# Shruthi-Analog-SMR4-mkII-12V-DO-NOT-BUIL.net
KiCad netlist of a schematic drawn in EAGLE
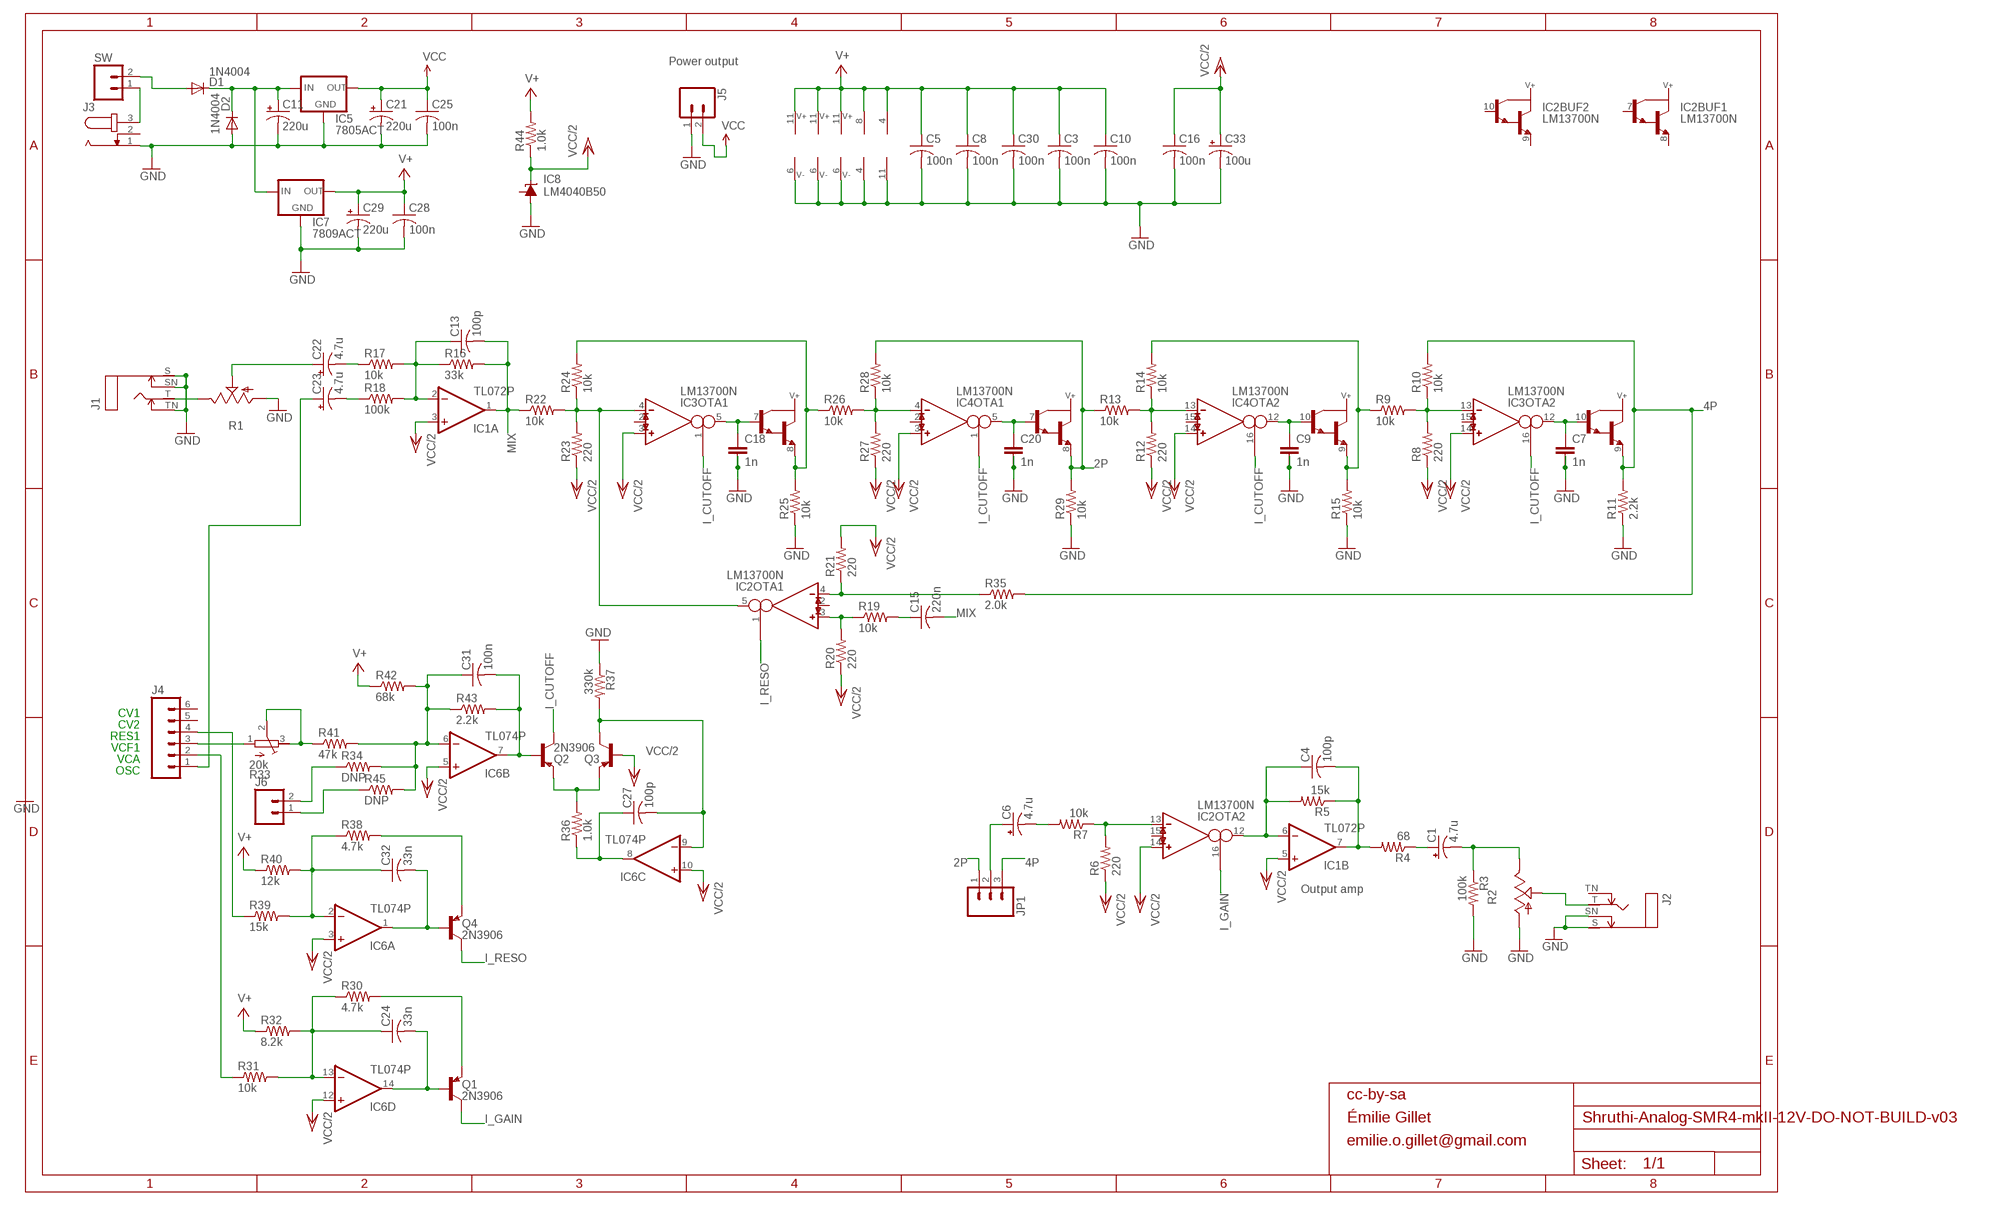
[diagram p0: schematic, sheet 1]

(export (version "E")
  (design (tool "Eeschema 10.0.6"))
  (components
    (comp (ref "C1")
      (value "4.7u")
      (footprint "eagle-import:E2,5-6")
      (libsource (lib "eagle-import") (part "CPOL-USE2.5-6"))
    )
    (comp (ref "C3")
      (value "100n")
      (footprint "eagle-import:C025-025X050")
      (libsource (lib "eagle-import") (part "C-US025-025X050"))
    )
    (comp (ref "C4")
      (value "100p")
      (footprint "eagle-import:C025-025X050")
      (libsource (lib "eagle-import") (part "C-US025-025X050"))
    )
    (comp (ref "C5")
      (value "100n")
      (footprint "eagle-import:C025-025X050")
      (libsource (lib "eagle-import") (part "C-US025-025X050"))
    )
    (comp (ref "C6")
      (value "4.7u")
      (footprint "eagle-import:E2,5-6")
      (libsource (lib "eagle-import") (part "CPOL-USE2.5-6"))
    )
    (comp (ref "C7")
      (value "1n")
      (footprint "eagle-import:C2.5_5-2")
      (libsource (lib "eagle-import") (part "C-2.5-5/2"))
    )
    (comp (ref "C8")
      (value "100n")
      (footprint "eagle-import:C025-025X050")
      (libsource (lib "eagle-import") (part "C-US025-025X050"))
    )
    (comp (ref "C9")
      (value "1n")
      (footprint "eagle-import:C2.5_5-2")
      (libsource (lib "eagle-import") (part "C-2.5-5/2"))
    )
    (comp (ref "C10")
      (value "100n")
      (footprint "eagle-import:C025-025X050")
      (libsource (lib "eagle-import") (part "C-US025-025X050"))
    )
    (comp (ref "C11")
      (value "220u")
      (footprint "eagle-import:E5-10,5")
      (libsource (lib "eagle-import") (part "CPOL-USE5-10.5"))
    )
    (comp (ref "C13")
      (value "100p")
      (footprint "eagle-import:C025-025X050")
      (libsource (lib "eagle-import") (part "C-US025-025X050"))
    )
    (comp (ref "C15")
      (value "220n")
      (footprint "eagle-import:C025-025X050")
      (libsource (lib "eagle-import") (part "C-US025-025X050"))
    )
    (comp (ref "C16")
      (value "100n")
      (footprint "eagle-import:C025-025X050")
      (libsource (lib "eagle-import") (part "C-US025-025X050"))
    )
    (comp (ref "C18")
      (value "1n")
      (footprint "eagle-import:C2.5_5-2")
      (libsource (lib "eagle-import") (part "C-2.5-5/2"))
    )
    (comp (ref "C20")
      (value "1n")
      (footprint "eagle-import:C2.5_5-2")
      (libsource (lib "eagle-import") (part "C-2.5-5/2"))
    )
    (comp (ref "C21")
      (value "220u")
      (footprint "eagle-import:E5-10,5")
      (libsource (lib "eagle-import") (part "CPOL-USE5-10.5"))
    )
    (comp (ref "C22")
      (value "4.7u")
      (footprint "eagle-import:E2,5-6")
      (libsource (lib "eagle-import") (part "CPOL-USE2.5-6"))
    )
    (comp (ref "C23")
      (value "4.7u")
      (footprint "eagle-import:E2,5-6")
      (libsource (lib "eagle-import") (part "CPOL-USE2.5-6"))
    )
    (comp (ref "C24")
      (value "33n")
      (footprint "eagle-import:C050-025X075")
      (libsource (lib "eagle-import") (part "C-US050-025X075"))
    )
    (comp (ref "C25")
      (value "100n")
      (footprint "eagle-import:C025-025X050")
      (libsource (lib "eagle-import") (part "C-US025-025X050"))
    )
    (comp (ref "C27")
      (value "100p")
      (footprint "eagle-import:C025-025X050")
      (libsource (lib "eagle-import") (part "C-US025-025X050"))
    )
    (comp (ref "C28")
      (value "100n")
      (footprint "eagle-import:C025-025X050")
      (libsource (lib "eagle-import") (part "C-US025-025X050"))
    )
    (comp (ref "C29")
      (value "220u")
      (footprint "eagle-import:E5-10,5")
      (libsource (lib "eagle-import") (part "CPOL-USE5-10.5"))
    )
    (comp (ref "C30")
      (value "100n")
      (footprint "eagle-import:C025-025X050")
      (libsource (lib "eagle-import") (part "C-US025-025X050"))
    )
    (comp (ref "C31")
      (value "100n")
      (footprint "eagle-import:C025-025X050")
      (libsource (lib "eagle-import") (part "C-US025-025X050"))
    )
    (comp (ref "C32")
      (value "33n")
      (footprint "eagle-import:C050-025X075")
      (libsource (lib "eagle-import") (part "C-US050-025X075"))
    )
    (comp (ref "C33")
      (value "100u")
      (footprint "eagle-import:E2,5-6")
      (libsource (lib "eagle-import") (part "CPOL-USE2.5-6"))
    )
    (comp (ref "D1")
      (value "1N4004")
      (footprint "eagle-import:DO41-10")
      (libsource (lib "eagle-import") (part "1N4004"))
    )
    (comp (ref "D2")
      (value "1N4004")
      (footprint "eagle-import:DO41-10")
      (libsource (lib "eagle-import") (part "1N4004"))
    )
    (comp (ref "IC1")
      (value "TL072P")
      (footprint "eagle-import:DIL08")
      (libsource (lib "eagle-import") (part "TL072P"))
    )
    (comp (ref "IC2")
      (value "LM13700N")
      (footprint "eagle-import:DIL16")
      (libsource (lib "eagle-import") (part "LM13700N"))
    )
    (comp (ref "IC3")
      (value "LM13700N")
      (footprint "eagle-import:DIL16")
      (libsource (lib "eagle-import") (part "LM13700N"))
    )
    (comp (ref "IC4")
      (value "LM13700N")
      (footprint "eagle-import:DIL16")
      (libsource (lib "eagle-import") (part "LM13700N"))
    )
    (comp (ref "IC5")
      (value "7805ACT")
      (footprint "eagle-import:78XXS")
      (libsource (lib "eagle-import") (part "78XXS"))
    )
    (comp (ref "IC6")
      (value "TL074P")
      (footprint "eagle-import:DIL14")
      (libsource (lib "eagle-import") (part "TL084P"))
    )
    (comp (ref "IC7")
      (value "7809ACT")
      (footprint "eagle-import:78XXS")
      (libsource (lib "eagle-import") (part "78XXS"))
    )
    (comp (ref "IC8")
      (value "LM4040B50")
      (footprint "eagle-import:LP_O-PBCY-W3")
      (libsource (lib "eagle-import") (part "LM4041ILPB"))
    )
    (comp (ref "J1")
      (value "MONOSWS")
      (footprint "eagle-import:NMJ4HC-S")
      (libsource (lib "eagle-import") (part "MONOSWS"))
    )
    (comp (ref "J2")
      (value "MONOSWS")
      (footprint "eagle-import:NMJ4HC-S")
      (libsource (lib "eagle-import") (part "MONOSWS"))
    )
    (comp (ref "J3")
      (value "JACK-PLUG2")
      (footprint "eagle-import:SPC4078_BIG_HOLES")
      (libsource (lib "eagle-import") (part "JACK-PLUG2"))
    )
    (comp (ref "J4")
      (value "M06SIP")
      (footprint "eagle-import:1X06")
      (libsource (lib "eagle-import") (part "M06SIP"))
    )
    (comp (ref "J5")
      (value "M02PTH")
      (footprint "eagle-import:1X02")
      (libsource (lib "eagle-import") (part "M02PTH"))
    )
    (comp (ref "J6")
      (value "M02PTH")
      (footprint "eagle-import:1X02")
      (libsource (lib "eagle-import") (part "M02PTH"))
    )
    (comp (ref "JP1")
      (value "M03PTH")
      (footprint "eagle-import:1X03")
      (libsource (lib "eagle-import") (part "M03PTH"))
    )
    (comp (ref "Q1")
      (value "2N3906")
      (footprint "eagle-import:TO92-")
      (libsource (lib "eagle-import") (part "2N3906-"))
    )
    (comp (ref "Q2")
      (value "2N3906")
      (footprint "eagle-import:TO92-")
      (libsource (lib "eagle-import") (part "2N3906-"))
    )
    (comp (ref "Q3")
      (value "2N3906")
      (footprint "eagle-import:TO92-")
      (libsource (lib "eagle-import") (part "2N3906-"))
    )
    (comp (ref "Q4")
      (value "2N3906")
      (footprint "eagle-import:TO92-")
      (libsource (lib "eagle-import") (part "2N3906-"))
    )
    (comp (ref "R1")
      (value "POT_USCABLED")
      (footprint "eagle-import:CABLE_POT_6MM")
      (libsource (lib "eagle-import") (part "POT_USCABLED"))
    )
    (comp (ref "R2")
      (value "POT_USCABLED")
      (footprint "eagle-import:CABLE_POT_6MM")
      (libsource (lib "eagle-import") (part "POT_USCABLED"))
    )
    (comp (ref "R3")
      (value "100k")
      (footprint "eagle-import:0204_7")
      (libsource (lib "eagle-import") (part "R-US_0204/7"))
    )
    (comp (ref "R4")
      (value "68")
      (footprint "eagle-import:0204_7")
      (libsource (lib "eagle-import") (part "R-US_0204/7"))
    )
    (comp (ref "R5")
      (value "15k")
      (footprint "eagle-import:0204_7")
      (libsource (lib "eagle-import") (part "R-US_0204/7"))
    )
    (comp (ref "R6")
      (value "220")
      (footprint "eagle-import:0204_7")
      (libsource (lib "eagle-import") (part "R-US_0204/7"))
    )
    (comp (ref "R7")
      (value "10k")
      (footprint "eagle-import:0204_7")
      (libsource (lib "eagle-import") (part "R-US_0204/7"))
    )
    (comp (ref "R8")
      (value "220")
      (footprint "eagle-import:0204_7")
      (libsource (lib "eagle-import") (part "R-US_0204/7"))
    )
    (comp (ref "R9")
      (value "10k")
      (footprint "eagle-import:0204_7")
      (libsource (lib "eagle-import") (part "R-US_0204/7"))
    )
    (comp (ref "R10")
      (value "10k")
      (footprint "eagle-import:0204_7")
      (libsource (lib "eagle-import") (part "R-US_0204/7"))
    )
    (comp (ref "R11")
      (value "2.2k")
      (footprint "eagle-import:0204_7")
      (libsource (lib "eagle-import") (part "R-US_0204/7"))
    )
    (comp (ref "R12")
      (value "220")
      (footprint "eagle-import:0204_7")
      (libsource (lib "eagle-import") (part "R-US_0204/7"))
    )
    (comp (ref "R13")
      (value "10k")
      (footprint "eagle-import:0204_7")
      (libsource (lib "eagle-import") (part "R-US_0204/7"))
    )
    (comp (ref "R14")
      (value "10k")
      (footprint "eagle-import:0204_7")
      (libsource (lib "eagle-import") (part "R-US_0204/7"))
    )
    (comp (ref "R15")
      (value "10k")
      (footprint "eagle-import:0204_7")
      (libsource (lib "eagle-import") (part "R-US_0204/7"))
    )
    (comp (ref "R16")
      (value "33k")
      (footprint "eagle-import:0204_7")
      (libsource (lib "eagle-import") (part "R-US_0204/7"))
    )
    (comp (ref "R17")
      (value "10k")
      (footprint "eagle-import:0204_7")
      (libsource (lib "eagle-import") (part "R-US_0204/7"))
    )
    (comp (ref "R18")
      (value "100k")
      (footprint "eagle-import:0204_7")
      (libsource (lib "eagle-import") (part "R-US_0204/7"))
    )
    (comp (ref "R19")
      (value "10k")
      (footprint "eagle-import:0204_7")
      (libsource (lib "eagle-import") (part "R-US_0204/7"))
    )
    (comp (ref "R20")
      (value "220")
      (footprint "eagle-import:0204_7")
      (libsource (lib "eagle-import") (part "R-US_0204/7"))
    )
    (comp (ref "R21")
      (value "220")
      (footprint "eagle-import:0204_7")
      (libsource (lib "eagle-import") (part "R-US_0204/7"))
    )
    (comp (ref "R22")
      (value "10k")
      (footprint "eagle-import:0204_7")
      (libsource (lib "eagle-import") (part "R-US_0204/7"))
    )
    (comp (ref "R23")
      (value "220")
      (footprint "eagle-import:0204_7")
      (libsource (lib "eagle-import") (part "R-US_0204/7"))
    )
    (comp (ref "R24")
      (value "10k")
      (footprint "eagle-import:0204_7")
      (libsource (lib "eagle-import") (part "R-US_0204/7"))
    )
    (comp (ref "R25")
      (value "10k")
      (footprint "eagle-import:0204_7")
      (libsource (lib "eagle-import") (part "R-US_0204/7"))
    )
    (comp (ref "R26")
      (value "10k")
      (footprint "eagle-import:0204_7")
      (libsource (lib "eagle-import") (part "R-US_0204/7"))
    )
    (comp (ref "R27")
      (value "220")
      (footprint "eagle-import:0204_7")
      (libsource (lib "eagle-import") (part "R-US_0204/7"))
    )
    (comp (ref "R28")
      (value "10k")
      (footprint "eagle-import:0204_7")
      (libsource (lib "eagle-import") (part "R-US_0204/7"))
    )
    (comp (ref "R29")
      (value "10k")
      (footprint "eagle-import:0204_7")
      (libsource (lib "eagle-import") (part "R-US_0204/7"))
    )
    (comp (ref "R30")
      (value "4.7k")
      (footprint "eagle-import:0204_7")
      (libsource (lib "eagle-import") (part "R-US_0204/7"))
    )
    (comp (ref "R31")
      (value "10k")
      (footprint "eagle-import:0204_7")
      (libsource (lib "eagle-import") (part "R-US_0204/7"))
    )
    (comp (ref "R32")
      (value "8.2k")
      (footprint "eagle-import:0204_7")
      (libsource (lib "eagle-import") (part "R-US_0204/7"))
    )
    (comp (ref "R33")
      (value "20k")
      (footprint "eagle-import:RTRIM3296W")
      (libsource (lib "eagle-import") (part "R-TRIMM3296W"))
    )
    (comp (ref "R34")
      (value "DNP")
      (footprint "eagle-import:0204V")
      (libsource (lib "eagle-import") (part "R-US_0204/2V"))
    )
    (comp (ref "R35")
      (value "2.0k")
      (footprint "eagle-import:0204_7")
      (libsource (lib "eagle-import") (part "R-US_0204/7"))
    )
    (comp (ref "R36")
      (value "1.0k")
      (footprint "eagle-import:0204_7")
      (libsource (lib "eagle-import") (part "R-US_0204/7"))
    )
    (comp (ref "R37")
      (value "330k")
      (footprint "eagle-import:0204_7")
      (libsource (lib "eagle-import") (part "R-US_0204/7"))
    )
    (comp (ref "R38")
      (value "4.7k")
      (footprint "eagle-import:0204_7")
      (libsource (lib "eagle-import") (part "R-US_0204/7"))
    )
    (comp (ref "R39")
      (value "15k")
      (footprint "eagle-import:0204_7")
      (libsource (lib "eagle-import") (part "R-US_0204/7"))
    )
    (comp (ref "R40")
      (value "12k")
      (footprint "eagle-import:0204_7")
      (libsource (lib "eagle-import") (part "R-US_0204/7"))
    )
    (comp (ref "R41")
      (value "47k")
      (footprint "eagle-import:0204_7")
      (libsource (lib "eagle-import") (part "R-US_0204/7"))
    )
    (comp (ref "R42")
      (value "68k")
      (footprint "eagle-import:0204_7")
      (libsource (lib "eagle-import") (part "R-US_0204/7"))
    )
    (comp (ref "R43")
      (value "2.2k")
      (footprint "eagle-import:0204_7")
      (libsource (lib "eagle-import") (part "R-US_0204/7"))
    )
    (comp (ref "R44")
      (value "1.0k")
      (footprint "eagle-import:0204_7")
      (libsource (lib "eagle-import") (part "R-US_0204/7"))
    )
    (comp (ref "R45")
      (value "DNP")
      (footprint "eagle-import:0204V")
      (libsource (lib "eagle-import") (part "R-US_0204/2V"))
    )
    (comp (ref "SW")
      (value "M02PTH")
      (footprint "eagle-import:1X02")
      (libsource (lib "eagle-import") (part "M02PTH"))
    )
  )
  (nets
    (net (code "1") (name "/2P") (class "Default")
      (node (ref "IC4") (pin "8") (pinfunction "E_8") (pintype "passive"))
      (node (ref "JP1") (pin "1") (pinfunction "1_1") (pintype "passive"))
      (node (ref "R13") (pin "1") (pinfunction "1_1") (pintype "passive"))
      (node (ref "R28") (pin "2") (pinfunction "2_2") (pintype "passive"))
      (node (ref "R29") (pin "2") (pinfunction "2_2") (pintype "passive"))
    )
    (net (code "2") (name "/4P") (class "Default")
      (node (ref "IC3") (pin "9") (pinfunction "E_9") (pintype "passive"))
      (node (ref "JP1") (pin "3") (pinfunction "3_3") (pintype "passive"))
      (node (ref "R10") (pin "2") (pinfunction "2_2") (pintype "passive"))
      (node (ref "R11") (pin "2") (pinfunction "2_2") (pintype "passive"))
      (node (ref "R35") (pin "2") (pinfunction "2_2") (pintype "passive"))
    )
    (net (code "3") (name "/I_CUTOFF") (class "Default")
      (node (ref "IC3") (pin "1") (pinfunction "I_BIAS_1") (pintype "input"))
      (node (ref "IC3") (pin "16") (pinfunction "I_BIAS_16") (pintype "input"))
      (node (ref "IC4") (pin "1") (pinfunction "I_BIAS_1") (pintype "input"))
      (node (ref "IC4") (pin "16") (pinfunction "I_BIAS_16") (pintype "input"))
      (node (ref "Q2") (pin "1") (pinfunction "C_1") (pintype "passive"))
    )
    (net (code "4") (name "/I_GAIN") (class "Default")
      (node (ref "IC2") (pin "16") (pinfunction "I_BIAS_16") (pintype "input"))
      (node (ref "Q1") (pin "1") (pinfunction "C_1") (pintype "passive"))
    )
    (net (code "5") (name "/I_RESO") (class "Default")
      (node (ref "IC2") (pin "1") (pinfunction "I_BIAS_1") (pintype "input"))
      (node (ref "Q4") (pin "1") (pinfunction "C_1") (pintype "passive"))
    )
    (net (code "6") (name "/MIX") (class "Default")
      (node (ref "C13") (pin "2") (pinfunction "2_2") (pintype "passive"))
      (node (ref "C15") (pin "2") (pinfunction "2_2") (pintype "passive"))
      (node (ref "IC1") (pin "1") (pinfunction "OUT_1") (pintype "output"))
      (node (ref "R16") (pin "2") (pinfunction "2_2") (pintype "passive"))
      (node (ref "R22") (pin "1") (pinfunction "1_1") (pintype "passive"))
    )
    (net (code "7") (name "GND") (class "Default")
      (node (ref "C10") (pin "2") (pinfunction "2_2") (pintype "passive"))
      (node (ref "C11") (pin "-") (pinfunction "-_-") (pintype "passive"))
      (node (ref "C16") (pin "2") (pinfunction "2_2") (pintype "passive"))
      (node (ref "C18") (pin "2") (pinfunction "2_2") (pintype "passive"))
      (node (ref "C18") (pin "3") (pinfunction "3_3") (pintype "passive"))
      (node (ref "C20") (pin "2") (pinfunction "2_2") (pintype "passive"))
      (node (ref "C20") (pin "3") (pinfunction "3_3") (pintype "passive"))
      (node (ref "C21") (pin "-") (pinfunction "-_-") (pintype "passive"))
      (node (ref "C25") (pin "2") (pinfunction "2_2") (pintype "passive"))
      (node (ref "C28") (pin "2") (pinfunction "2_2") (pintype "passive"))
      (node (ref "C29") (pin "-") (pinfunction "-_-") (pintype "passive"))
      (node (ref "C3") (pin "2") (pinfunction "2_2") (pintype "passive"))
      (node (ref "C30") (pin "2") (pinfunction "2_2") (pintype "passive"))
      (node (ref "C33") (pin "-") (pinfunction "-_-") (pintype "passive"))
      (node (ref "C5") (pin "2") (pinfunction "2_2") (pintype "passive"))
      (node (ref "C7") (pin "2") (pinfunction "2_2") (pintype "passive"))
      (node (ref "C7") (pin "3") (pinfunction "3_3") (pintype "passive"))
      (node (ref "C8") (pin "2") (pinfunction "2_2") (pintype "passive"))
      (node (ref "C9") (pin "2") (pinfunction "2_2") (pintype "passive"))
      (node (ref "C9") (pin "3") (pinfunction "3_3") (pintype "passive"))
      (node (ref "D2") (pin "A") (pinfunction "A_A") (pintype "passive"))
      (node (ref "IC1") (pin "4") (pinfunction "V-_4") (pintype "power_in"))
      (node (ref "IC2") (pin "6") (pinfunction "V-_6") (pintype "power_in"))
      (node (ref "IC3") (pin "6") (pinfunction "V-_6") (pintype "power_in"))
      (node (ref "IC4") (pin "6") (pinfunction "V-_6") (pintype "power_in"))
      (node (ref "IC5") (pin "GND") (pinfunction "GND_GND") (pintype "input"))
      (node (ref "IC6") (pin "11") (pinfunction "V-_11") (pintype "power_in"))
      (node (ref "IC7") (pin "GND") (pinfunction "GND_GND") (pintype "input"))
      (node (ref "IC8") (pin "3") (pinfunction "A_3") (pintype "passive"))
      (node (ref "J1") (pin "S") (pinfunction "S_S") (pintype "passive"))
      (node (ref "J1") (pin "SN") (pinfunction "SN_SN") (pintype "passive"))
      (node (ref "J1") (pin "TN") (pinfunction "TN_TN") (pintype "passive"))
      (node (ref "J2") (pin "S") (pinfunction "S_S") (pintype "passive"))
      (node (ref "J2") (pin "SN") (pinfunction "SN_SN") (pintype "passive"))
      (node (ref "J3") (pin "1") (pinfunction "1_1") (pintype "passive"))
      (node (ref "J5") (pin "1") (pinfunction "1_1") (pintype "passive"))
      (node (ref "R1") (pin "A") (pinfunction "A_A") (pintype "passive"))
      (node (ref "R11") (pin "1") (pinfunction "1_1") (pintype "passive"))
      (node (ref "R15") (pin "1") (pinfunction "1_1") (pintype "passive"))
      (node (ref "R2") (pin "A") (pinfunction "A_A") (pintype "passive"))
      (node (ref "R25") (pin "1") (pinfunction "1_1") (pintype "passive"))
      (node (ref "R29") (pin "1") (pinfunction "1_1") (pintype "passive"))
      (node (ref "R3") (pin "2") (pinfunction "2_2") (pintype "passive"))
      (node (ref "R37") (pin "1") (pinfunction "1_1") (pintype "passive"))
    )
    (net (code "8") (name "Net-(C1-Pad+)") (class "Default")
      (node (ref "C1") (pin "+") (pinfunction "+_+") (pintype "passive"))
      (node (ref "R4") (pin "1") (pinfunction "1_1") (pintype "passive"))
    )
    (net (code "9") (name "Net-(C1-Pad-)") (class "Default")
      (node (ref "C1") (pin "-") (pinfunction "-_-") (pintype "passive"))
      (node (ref "R2") (pin "E") (pinfunction "E_E") (pintype "passive"))
      (node (ref "R3") (pin "1") (pinfunction "1_1") (pintype "passive"))
    )
    (net (code "10") (name "Net-(C6-Pad+)") (class "Default")
      (node (ref "C6") (pin "+") (pinfunction "+_+") (pintype "passive"))
      (node (ref "JP1") (pin "2") (pinfunction "2_2") (pintype "passive"))
    )
    (net (code "11") (name "Net-(C6-Pad-)") (class "Default")
      (node (ref "C6") (pin "-") (pinfunction "-_-") (pintype "passive"))
      (node (ref "R7") (pin "2") (pinfunction "2_2") (pintype "passive"))
    )
    (net (code "12") (name "Net-(C11-Pad+)") (class "Default")
      (node (ref "C11") (pin "+") (pinfunction "+_+") (pintype "passive"))
      (node (ref "D1") (pin "C") (pinfunction "C_C") (pintype "passive"))
      (node (ref "D2") (pin "C") (pinfunction "C_C") (pintype "passive"))
      (node (ref "IC5") (pin "IN") (pinfunction "IN_IN") (pintype "input"))
      (node (ref "IC7") (pin "IN") (pinfunction "IN_IN") (pintype "input"))
    )
    (net (code "13") (name "Net-(C15-Pad1)") (class "Default")
      (node (ref "C15") (pin "1") (pinfunction "1_1") (pintype "passive"))
      (node (ref "R19") (pin "2") (pinfunction "2_2") (pintype "passive"))
    )
    (net (code "14") (name "Net-(C22-Pad+)") (class "Default")
      (node (ref "C22") (pin "+") (pinfunction "+_+") (pintype "passive"))
      (node (ref "R1") (pin "S") (pinfunction "S_S") (pintype "passive"))
    )
    (net (code "15") (name "Net-(C22-Pad-)") (class "Default")
      (node (ref "C22") (pin "-") (pinfunction "-_-") (pintype "passive"))
      (node (ref "R17") (pin "1") (pinfunction "1_1") (pintype "passive"))
    )
    (net (code "16") (name "Net-(C23-Pad+)") (class "Default")
      (node (ref "C23") (pin "+") (pinfunction "+_+") (pintype "passive"))
      (node (ref "J4") (pin "1") (pinfunction "1_1") (pintype "passive"))
    )
    (net (code "17") (name "Net-(C23-Pad-)") (class "Default")
      (node (ref "C23") (pin "-") (pinfunction "-_-") (pintype "passive"))
      (node (ref "R18") (pin "1") (pinfunction "1_1") (pintype "passive"))
    )
    (net (code "18") (name "Net-(D1-PadA)") (class "Default")
      (node (ref "D1") (pin "A") (pinfunction "A_A") (pintype "passive"))
      (node (ref "SW") (pin "2") (pinfunction "2_2") (pintype "passive"))
    )
    (net (code "19") (name "Net-(IC1A--IN)") (class "Default")
      (node (ref "C13") (pin "1") (pinfunction "1_1") (pintype "passive"))
      (node (ref "IC1") (pin "2") (pinfunction "-IN_2") (pintype "input"))
      (node (ref "R16") (pin "1") (pinfunction "1_1") (pintype "passive"))
      (node (ref "R17") (pin "2") (pinfunction "2_2") (pintype "passive"))
      (node (ref "R18") (pin "2") (pinfunction "2_2") (pintype "passive"))
    )
    (net (code "20") (name "Net-(IC1B--IN)") (class "Default")
      (node (ref "C4") (pin "1") (pinfunction "1_1") (pintype "passive"))
      (node (ref "IC1") (pin "6") (pinfunction "-IN_6") (pintype "input"))
      (node (ref "IC2") (pin "12") (pinfunction "OUT_12") (pintype "output"))
      (node (ref "R5") (pin "2") (pinfunction "2_2") (pintype "passive"))
    )
    (net (code "21") (name "Net-(IC1B-OUT)") (class "Default")
      (node (ref "C4") (pin "2") (pinfunction "2_2") (pintype "passive"))
      (node (ref "IC1") (pin "7") (pinfunction "OUT_7") (pintype "output"))
      (node (ref "R4") (pin "2") (pinfunction "2_2") (pintype "passive"))
      (node (ref "R5") (pin "1") (pinfunction "1_1") (pintype "passive"))
    )
    (net (code "22") (name "Net-(IC2C-IN_N)") (class "Default")
      (node (ref "IC2") (pin "4") (pinfunction "IN_N_4") (pintype "input"))
      (node (ref "R21") (pin "1") (pinfunction "1_1") (pintype "passive"))
      (node (ref "R35") (pin "1") (pinfunction "1_1") (pintype "passive"))
    )
    (net (code "23") (name "Net-(IC2C-IN_P)") (class "Default")
      (node (ref "IC2") (pin "3") (pinfunction "IN_P_3") (pintype "input"))
      (node (ref "R19") (pin "1") (pinfunction "1_1") (pintype "passive"))
      (node (ref "R20") (pin "2") (pinfunction "2_2") (pintype "passive"))
    )
    (net (code "24") (name "Net-(IC2C-OUT)") (class "Default")
      (node (ref "IC2") (pin "5") (pinfunction "OUT_5") (pintype "output"))
      (node (ref "IC3") (pin "4") (pinfunction "IN_N_4") (pintype "input"))
      (node (ref "R22") (pin "2") (pinfunction "2_2") (pintype "passive"))
      (node (ref "R23") (pin "2") (pinfunction "2_2") (pintype "passive"))
      (node (ref "R24") (pin "1") (pinfunction "1_1") (pintype "passive"))
    )
    (net (code "25") (name "Net-(IC2D-IN_N)") (class "Default")
      (node (ref "IC2") (pin "13") (pinfunction "IN_N_13") (pintype "input"))
      (node (ref "R6") (pin "2") (pinfunction "2_2") (pintype "passive"))
      (node (ref "R7") (pin "1") (pinfunction "1_1") (pintype "passive"))
    )
    (net (code "26") (name "Net-(IC3A-B)") (class "Default")
      (node (ref "C18") (pin "1") (pinfunction "1_1") (pintype "passive"))
      (node (ref "IC3") (pin "5") (pinfunction "OUT_5") (pintype "output"))
      (node (ref "IC3") (pin "7") (pinfunction "B_7") (pintype "passive"))
    )
    (net (code "27") (name "Net-(IC3A-E)") (class "Default")
      (node (ref "IC3") (pin "8") (pinfunction "E_8") (pintype "passive"))
      (node (ref "R24") (pin "2") (pinfunction "2_2") (pintype "passive"))
      (node (ref "R25") (pin "2") (pinfunction "2_2") (pintype "passive"))
      (node (ref "R26") (pin "1") (pinfunction "1_1") (pintype "passive"))
    )
    (net (code "28") (name "Net-(IC3B-B)") (class "Default")
      (node (ref "C7") (pin "1") (pinfunction "1_1") (pintype "passive"))
      (node (ref "IC3") (pin "10") (pinfunction "B_10") (pintype "passive"))
      (node (ref "IC3") (pin "12") (pinfunction "OUT_12") (pintype "output"))
    )
    (net (code "29") (name "Net-(IC3D-IN_N)") (class "Default")
      (node (ref "IC3") (pin "13") (pinfunction "IN_N_13") (pintype "input"))
      (node (ref "R10") (pin "1") (pinfunction "1_1") (pintype "passive"))
      (node (ref "R8") (pin "2") (pinfunction "2_2") (pintype "passive"))
      (node (ref "R9") (pin "2") (pinfunction "2_2") (pintype "passive"))
    )
    (net (code "30") (name "Net-(IC4A-B)") (class "Default")
      (node (ref "C20") (pin "1") (pinfunction "1_1") (pintype "passive"))
      (node (ref "IC4") (pin "5") (pinfunction "OUT_5") (pintype "output"))
      (node (ref "IC4") (pin "7") (pinfunction "B_7") (pintype "passive"))
    )
    (net (code "31") (name "Net-(IC4B-B)") (class "Default")
      (node (ref "C9") (pin "1") (pinfunction "1_1") (pintype "passive"))
      (node (ref "IC4") (pin "10") (pinfunction "B_10") (pintype "passive"))
      (node (ref "IC4") (pin "12") (pinfunction "OUT_12") (pintype "output"))
    )
    (net (code "32") (name "Net-(IC4B-E)") (class "Default")
      (node (ref "IC4") (pin "9") (pinfunction "E_9") (pintype "passive"))
      (node (ref "R14") (pin "2") (pinfunction "2_2") (pintype "passive"))
      (node (ref "R15") (pin "2") (pinfunction "2_2") (pintype "passive"))
      (node (ref "R9") (pin "1") (pinfunction "1_1") (pintype "passive"))
    )
    (net (code "33") (name "Net-(IC4C-IN_N)") (class "Default")
      (node (ref "IC4") (pin "4") (pinfunction "IN_N_4") (pintype "input"))
      (node (ref "R26") (pin "2") (pinfunction "2_2") (pintype "passive"))
      (node (ref "R27") (pin "2") (pinfunction "2_2") (pintype "passive"))
      (node (ref "R28") (pin "1") (pinfunction "1_1") (pintype "passive"))
    )
    (net (code "34") (name "Net-(IC4D-IN_N)") (class "Default")
      (node (ref "IC4") (pin "13") (pinfunction "IN_N_13") (pintype "input"))
      (node (ref "R12") (pin "2") (pinfunction "2_2") (pintype "passive"))
      (node (ref "R13") (pin "2") (pinfunction "2_2") (pintype "passive"))
      (node (ref "R14") (pin "1") (pinfunction "1_1") (pintype "passive"))
    )
    (net (code "35") (name "Net-(IC6A--IN)") (class "Default")
      (node (ref "C32") (pin "1") (pinfunction "1_1") (pintype "passive"))
      (node (ref "IC6") (pin "2") (pinfunction "-IN_2") (pintype "input"))
      (node (ref "R38") (pin "1") (pinfunction "1_1") (pintype "passive"))
      (node (ref "R39") (pin "2") (pinfunction "2_2") (pintype "passive"))
      (node (ref "R40") (pin "2") (pinfunction "2_2") (pintype "passive"))
    )
    (net (code "36") (name "Net-(IC6A-OUT)") (class "Default")
      (node (ref "C32") (pin "2") (pinfunction "2_2") (pintype "passive"))
      (node (ref "IC6") (pin "1") (pinfunction "OUT_1") (pintype "output"))
      (node (ref "Q4") (pin "2") (pinfunction "B_2") (pintype "passive"))
    )
    (net (code "37") (name "Net-(IC6B--IN)") (class "Default")
      (node (ref "C31") (pin "1") (pinfunction "1_1") (pintype "passive"))
      (node (ref "IC6") (pin "6") (pinfunction "-IN_6") (pintype "input"))
      (node (ref "R34") (pin "2") (pinfunction "2_2") (pintype "passive"))
      (node (ref "R41") (pin "2") (pinfunction "2_2") (pintype "passive"))
      (node (ref "R42") (pin "2") (pinfunction "2_2") (pintype "passive"))
      (node (ref "R43") (pin "1") (pinfunction "1_1") (pintype "passive"))
      (node (ref "R45") (pin "2") (pinfunction "2_2") (pintype "passive"))
    )
    (net (code "38") (name "Net-(IC6B-OUT)") (class "Default")
      (node (ref "C31") (pin "2") (pinfunction "2_2") (pintype "passive"))
      (node (ref "IC6") (pin "7") (pinfunction "OUT_7") (pintype "output"))
      (node (ref "Q2") (pin "2") (pinfunction "B_2") (pintype "passive"))
      (node (ref "R43") (pin "2") (pinfunction "2_2") (pintype "passive"))
    )
    (net (code "39") (name "Net-(IC6C--IN)") (class "Default")
      (node (ref "C27") (pin "2") (pinfunction "2_2") (pintype "passive"))
      (node (ref "IC6") (pin "9") (pinfunction "-IN_9") (pintype "input"))
      (node (ref "Q3") (pin "1") (pinfunction "C_1") (pintype "passive"))
      (node (ref "R37") (pin "2") (pinfunction "2_2") (pintype "passive"))
    )
    (net (code "40") (name "Net-(IC6C-OUT)") (class "Default")
      (node (ref "C27") (pin "1") (pinfunction "1_1") (pintype "passive"))
      (node (ref "IC6") (pin "8") (pinfunction "OUT_8") (pintype "output"))
      (node (ref "R36") (pin "1") (pinfunction "1_1") (pintype "passive"))
    )
    (net (code "41") (name "Net-(IC6D--IN)") (class "Default")
      (node (ref "C24") (pin "1") (pinfunction "1_1") (pintype "passive"))
      (node (ref "IC6") (pin "13") (pinfunction "-IN_13") (pintype "input"))
      (node (ref "R30") (pin "1") (pinfunction "1_1") (pintype "passive"))
      (node (ref "R31") (pin "2") (pinfunction "2_2") (pintype "passive"))
      (node (ref "R32") (pin "2") (pinfunction "2_2") (pintype "passive"))
    )
    (net (code "42") (name "Net-(IC6D-OUT)") (class "Default")
      (node (ref "C24") (pin "2") (pinfunction "2_2") (pintype "passive"))
      (node (ref "IC6") (pin "14") (pinfunction "OUT_14") (pintype "output"))
      (node (ref "Q1") (pin "2") (pinfunction "B_2") (pintype "passive"))
    )
    (net (code "43") (name "Net-(J1-PadT)") (class "Default")
      (node (ref "J1") (pin "T") (pinfunction "T_T") (pintype "passive"))
      (node (ref "R1") (pin "E") (pinfunction "E_E") (pintype "passive"))
    )
    (net (code "44") (name "Net-(J2-PadT)") (class "Default")
      (node (ref "J2") (pin "T") (pinfunction "T_T") (pintype "passive"))
      (node (ref "R2") (pin "S") (pinfunction "S_S") (pintype "passive"))
    )
    (net (code "45") (name "Net-(J3-Pad3)") (class "Default")
      (node (ref "J3") (pin "3") (pinfunction "3_3") (pintype "passive"))
      (node (ref "SW") (pin "1") (pinfunction "1_1") (pintype "passive"))
    )
    (net (code "46") (name "Net-(J4-Pad2)") (class "Default")
      (node (ref "J4") (pin "2") (pinfunction "2_2") (pintype "passive"))
      (node (ref "R31") (pin "1") (pinfunction "1_1") (pintype "passive"))
    )
    (net (code "47") (name "Net-(J4-Pad4)") (class "Default")
      (node (ref "J4") (pin "4") (pinfunction "4_4") (pintype "passive"))
      (node (ref "R39") (pin "1") (pinfunction "1_1") (pintype "passive"))
    )
    (net (code "48") (name "Net-(J6-Pad1)") (class "Default")
      (node (ref "J6") (pin "1") (pinfunction "1_1") (pintype "passive"))
      (node (ref "R45") (pin "1") (pinfunction "1_1") (pintype "passive"))
    )
    (net (code "49") (name "Net-(J6-Pad2)") (class "Default")
      (node (ref "J6") (pin "2") (pinfunction "2_2") (pintype "passive"))
      (node (ref "R34") (pin "1") (pinfunction "1_1") (pintype "passive"))
    )
    (net (code "50") (name "Net-(Q1-E)") (class "Default")
      (node (ref "Q1") (pin "3") (pinfunction "E_3") (pintype "passive"))
      (node (ref "R30") (pin "2") (pinfunction "2_2") (pintype "passive"))
    )
    (net (code "51") (name "Net-(Q2-E)") (class "Default")
      (node (ref "Q2") (pin "3") (pinfunction "E_3") (pintype "passive"))
      (node (ref "Q3") (pin "3") (pinfunction "E_3") (pintype "passive"))
      (node (ref "R36") (pin "2") (pinfunction "2_2") (pintype "passive"))
    )
    (net (code "52") (name "Net-(Q4-E)") (class "Default")
      (node (ref "Q4") (pin "3") (pinfunction "E_3") (pintype "passive"))
      (node (ref "R38") (pin "2") (pinfunction "2_2") (pintype "passive"))
    )
    (net (code "53") (name "Net-(R33-A)") (class "Default")
      (node (ref "R33") (pin "2") (pinfunction "S_2") (pintype "passive"))
      (node (ref "R33") (pin "3") (pinfunction "A_3") (pintype "passive"))
      (node (ref "R41") (pin "1") (pinfunction "1_1") (pintype "passive"))
    )
    (net (code "54") (name "Net-(R33-E)") (class "Default")
      (node (ref "J4") (pin "3") (pinfunction "3_3") (pintype "passive"))
      (node (ref "R33") (pin "1") (pinfunction "E_1") (pintype "passive"))
    )
    (net (code "55") (name "V+") (class "Default")
      (node (ref "C10") (pin "1") (pinfunction "1_1") (pintype "passive"))
      (node (ref "C28") (pin "1") (pinfunction "1_1") (pintype "passive"))
      (node (ref "C29") (pin "+") (pinfunction "+_+") (pintype "passive"))
      (node (ref "C3") (pin "1") (pinfunction "1_1") (pintype "passive"))
      (node (ref "C30") (pin "1") (pinfunction "1_1") (pintype "passive"))
      (node (ref "C5") (pin "1") (pinfunction "1_1") (pintype "passive"))
      (node (ref "C8") (pin "1") (pinfunction "1_1") (pintype "passive"))
      (node (ref "IC1") (pin "8") (pinfunction "V+_8") (pintype "power_in"))
      (node (ref "IC2") (pin "11") (pinfunction "V+_11") (pintype "power_in"))
      (node (ref "IC3") (pin "11") (pinfunction "V+_11") (pintype "power_in"))
      (node (ref "IC4") (pin "11") (pinfunction "V+_11") (pintype "power_in"))
      (node (ref "IC6") (pin "4") (pinfunction "V+_4") (pintype "power_in"))
      (node (ref "IC7") (pin "OUT") (pinfunction "OUT_OUT") (pintype "passive"))
      (node (ref "R32") (pin "1") (pinfunction "1_1") (pintype "passive"))
      (node (ref "R40") (pin "1") (pinfunction "1_1") (pintype "passive"))
      (node (ref "R42") (pin "1") (pinfunction "1_1") (pintype "passive"))
      (node (ref "R44") (pin "2") (pinfunction "2_2") (pintype "passive"))
    )
    (net (code "56") (name "VCC") (class "Default")
      (node (ref "C21") (pin "+") (pinfunction "+_+") (pintype "passive"))
      (node (ref "C25") (pin "1") (pinfunction "1_1") (pintype "passive"))
      (node (ref "IC5") (pin "OUT") (pinfunction "OUT_OUT") (pintype "passive"))
      (node (ref "J5") (pin "2") (pinfunction "2_2") (pintype "passive"))
    )
    (net (code "57") (name "VCC{slash}2") (class "Default")
      (node (ref "C16") (pin "1") (pinfunction "1_1") (pintype "passive"))
      (node (ref "C33") (pin "+") (pinfunction "+_+") (pintype "passive"))
      (node (ref "IC1") (pin "3") (pinfunction "+IN_3") (pintype "input"))
      (node (ref "IC1") (pin "5") (pinfunction "+IN_5") (pintype "input"))
      (node (ref "IC2") (pin "14") (pinfunction "IN_P_14") (pintype "input"))
      (node (ref "IC3") (pin "14") (pinfunction "IN_P_14") (pintype "input"))
      (node (ref "IC3") (pin "3") (pinfunction "IN_P_3") (pintype "input"))
      (node (ref "IC4") (pin "14") (pinfunction "IN_P_14") (pintype "input"))
      (node (ref "IC4") (pin "3") (pinfunction "IN_P_3") (pintype "input"))
      (node (ref "IC6") (pin "10") (pinfunction "+IN_10") (pintype "input"))
      (node (ref "IC6") (pin "12") (pinfunction "+IN_12") (pintype "input"))
      (node (ref "IC6") (pin "3") (pinfunction "+IN_3") (pintype "input"))
      (node (ref "IC6") (pin "5") (pinfunction "+IN_5") (pintype "input"))
      (node (ref "IC8") (pin "2") (pinfunction "C_2") (pintype "passive"))
      (node (ref "Q3") (pin "2") (pinfunction "B_2") (pintype "passive"))
      (node (ref "R12") (pin "1") (pinfunction "1_1") (pintype "passive"))
      (node (ref "R20") (pin "1") (pinfunction "1_1") (pintype "passive"))
      (node (ref "R21") (pin "2") (pinfunction "2_2") (pintype "passive"))
      (node (ref "R23") (pin "1") (pinfunction "1_1") (pintype "passive"))
      (node (ref "R27") (pin "1") (pinfunction "1_1") (pintype "passive"))
      (node (ref "R44") (pin "1") (pinfunction "1_1") (pintype "passive"))
      (node (ref "R6") (pin "1") (pinfunction "1_1") (pintype "passive"))
      (node (ref "R8") (pin "1") (pinfunction "1_1") (pintype "passive"))
    )
    (net (code "58") (name "unconnected-(IC2A-B-Pad7)") (class "Default")
      (node (ref "IC2") (pin "7") (pinfunction "B_7") (pintype "passive"))
    )
    (net (code "59") (name "unconnected-(IC2A-E-Pad8)") (class "Default")
      (node (ref "IC2") (pin "8") (pinfunction "E_8") (pintype "passive"))
    )
    (net (code "60") (name "unconnected-(IC2B-B-Pad10)") (class "Default")
      (node (ref "IC2") (pin "10") (pinfunction "B_10") (pintype "passive"))
    )
    (net (code "61") (name "unconnected-(IC2B-E-Pad9)") (class "Default")
      (node (ref "IC2") (pin "9") (pinfunction "E_9") (pintype "passive"))
    )
    (net (code "62") (name "unconnected-(IC2C-I_DIODE-Pad2)") (class "Default")
      (node (ref "IC2") (pin "2") (pinfunction "I_DIODE_2") (pintype "input"))
    )
    (net (code "63") (name "unconnected-(IC2D-I_DIODE-Pad15)") (class "Default")
      (node (ref "IC2") (pin "15") (pinfunction "I_DIODE_15") (pintype "input"))
    )
    (net (code "64") (name "unconnected-(IC3C-I_DIODE-Pad2)") (class "Default")
      (node (ref "IC3") (pin "2") (pinfunction "I_DIODE_2") (pintype "input"))
    )
    (net (code "65") (name "unconnected-(IC3D-I_DIODE-Pad15)") (class "Default")
      (node (ref "IC3") (pin "15") (pinfunction "I_DIODE_15") (pintype "input"))
    )
    (net (code "66") (name "unconnected-(IC4C-I_DIODE-Pad2)") (class "Default")
      (node (ref "IC4") (pin "2") (pinfunction "I_DIODE_2") (pintype "input"))
    )
    (net (code "67") (name "unconnected-(IC4D-I_DIODE-Pad15)") (class "Default")
      (node (ref "IC4") (pin "15") (pinfunction "I_DIODE_15") (pintype "input"))
    )
    (net (code "68") (name "unconnected-(IC8-FB-Pad1)") (class "Default")
      (node (ref "IC8") (pin "1") (pinfunction "FB_1") (pintype "passive"))
    )
    (net (code "69") (name "unconnected-(J2-PadTN)") (class "Default")
      (node (ref "J2") (pin "TN") (pinfunction "TN_TN") (pintype "passive"))
    )
    (net (code "70") (name "unconnected-(J3-Pad2)") (class "Default")
      (node (ref "J3") (pin "2") (pinfunction "2_2") (pintype "passive"))
    )
    (net (code "71") (name "unconnected-(J4-Pad5)") (class "Default")
      (node (ref "J4") (pin "5") (pinfunction "5_5") (pintype "passive"))
    )
    (net (code "72") (name "unconnected-(J4-Pad6)") (class "Default")
      (node (ref "J4") (pin "6") (pinfunction "6_6") (pintype "passive"))
    )
  )
)
